# motor_drive.net
KiCad netlist of a schematic drawn in Altium Designer
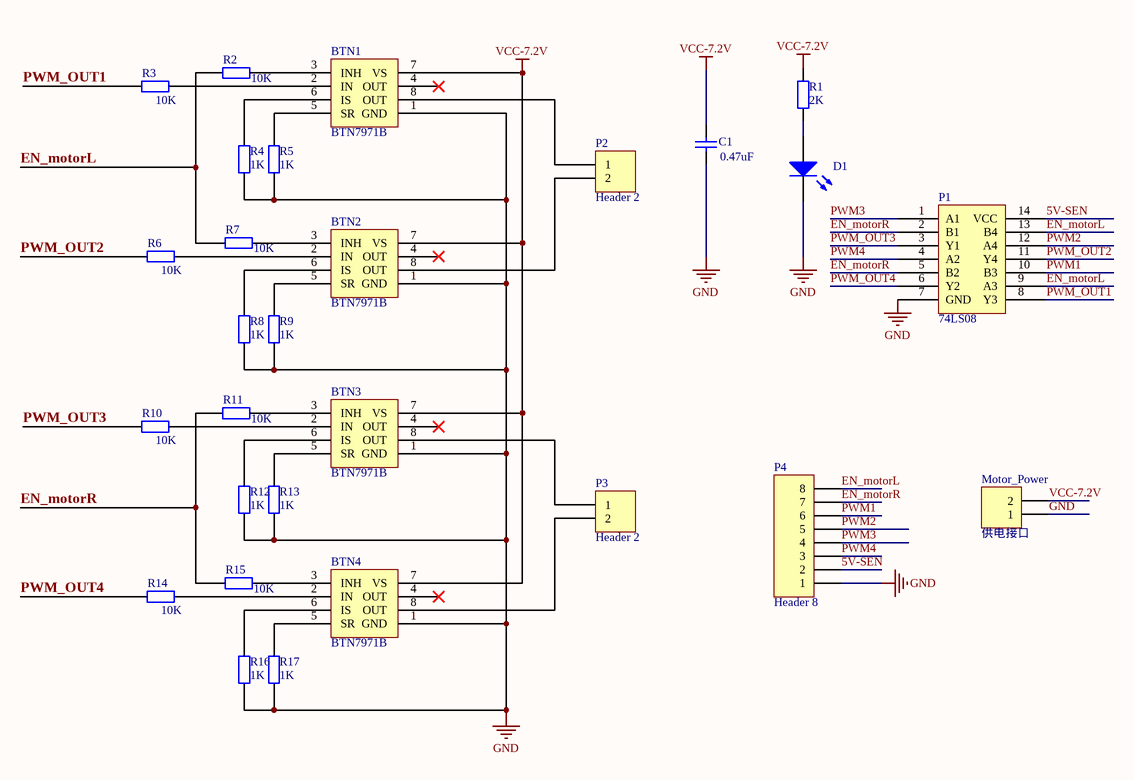
[diagram p0: motor_drive.SchDoc]

(export (version "E")
  (design (tool "Eeschema 10.0.6"))
  (components
    (comp (ref "BTN1") (value "BTN7971B") (footprint "TO-263-7") (libsource (lib "") (part "Component_1_1")))
    (comp (ref "BTN2") (value "BTN7971B") (footprint "TO-263-7") (libsource (lib "") (part "Component_1_1")))
    (comp (ref "BTN3") (value "BTN7971B") (footprint "TO-263-7") (libsource (lib "") (part "Component_1_1")))
    (comp (ref "BTN4") (value "BTN7971B") (footprint "TO-263-7") (libsource (lib "") (part "Component_1_1")))
    (comp (ref "C1")
      (value "0.47uF")
      (footprint "3216")
      (description "Capacitor")
      (fields (field (name "Comment") "Cap") (field (name "PUBLISHER") "Altium Limited"))
      (libsource (lib "Miscellaneous Devices") (part "Cap"))
    )
    (comp (ref "D1")
      (value "LED3")
      (footprint "C-0805")
      (description "Typical BLUE SiC LED")
      (fields (field (name "PUBLISHER") "Altium Limited"))
      (libsource (lib "Miscellaneous Devices") (part "LED3"))
    )
    (comp (ref "Motor_Power")
      (value "供电接口")
      (footprint "P_Header")
      (description "Header, 2-Pin")
      (fields (field (name "PUBLISHER") "Altium Limited"))
      (libsource (lib "Miscellaneous Connectors") (part "Header 2"))
    )
    (comp (ref "P1") (value "74LS08") (footprint "DIP-14") (libsource (lib "库1") (part "Component_1")))
    (comp (ref "P2")
      (value "Header 2")
      (footprint "PCBComponent_1")
      (libsource (lib "Schlib1") (part "Component_1"))
    )
    (comp (ref "P3")
      (value "Header 2")
      (footprint "PCBComponent_1")
      (libsource (lib "Schlib1") (part "Component_1"))
    )
    (comp (ref "P4")
      (value "Header 8")
      (footprint "HDR1X8")
      (description "Header, 8-Pin")
      (fields (field (name "PUBLISHER") "Altium Limited"))
      (libsource (lib "Miscellaneous Connectors") (part "Header 8"))
    )
    (comp (ref "R1")
      (value "2K")
      (footprint "0805")
      (description "Resistor")
      (fields (field (name "Comment") "Res2") (field (name "PUBLISHER") "Altium Limited"))
      (libsource (lib "Miscellaneous Devices") (part "Res2"))
    )
    (comp (ref "R2")
      (value "10K")
      (footprint "0805")
      (description "Resistor")
      (fields (field (name "Comment") "Res2") (field (name "PUBLISHER") "Altium Limited"))
      (libsource (lib "") (part "Res2_1"))
    )
    (comp (ref "R3")
      (value "10K")
      (footprint "0805")
      (description "Resistor")
      (fields (field (name "Comment") "Res2") (field (name "PUBLISHER") "Altium Limited"))
      (libsource (lib "") (part "Res2_1"))
    )
    (comp (ref "R4")
      (value "1K")
      (footprint "0805")
      (description "Resistor")
      (fields (field (name "Comment") "Res2") (field (name "PUBLISHER") "Altium Limited"))
      (libsource (lib "Miscellaneous Devices") (part "Res2"))
    )
    (comp (ref "R5")
      (value "1K")
      (footprint "0805")
      (description "Resistor")
      (fields (field (name "Comment") "Res2") (field (name "PUBLISHER") "Altium Limited"))
      (libsource (lib "Miscellaneous Devices") (part "Res2"))
    )
    (comp (ref "R6")
      (value "10K")
      (footprint "0805")
      (description "Resistor")
      (fields (field (name "Comment") "Res2") (field (name "PUBLISHER") "Altium Limited"))
      (libsource (lib "") (part "Res2_1"))
    )
    (comp (ref "R7")
      (value "10K")
      (footprint "0805")
      (description "Resistor")
      (fields (field (name "Comment") "Res2") (field (name "PUBLISHER") "Altium Limited"))
      (libsource (lib "") (part "Res2_1"))
    )
    (comp (ref "R8")
      (value "1K")
      (footprint "0805")
      (description "Resistor")
      (fields (field (name "Comment") "Res2") (field (name "PUBLISHER") "Altium Limited"))
      (libsource (lib "Miscellaneous Devices") (part "Res2"))
    )
    (comp (ref "R9")
      (value "1K")
      (footprint "0805")
      (description "Resistor")
      (fields (field (name "Comment") "Res2") (field (name "PUBLISHER") "Altium Limited"))
      (libsource (lib "Miscellaneous Devices") (part "Res2"))
    )
    (comp (ref "R10")
      (value "10K")
      (footprint "0805")
      (description "Resistor")
      (fields (field (name "Comment") "Res2") (field (name "PUBLISHER") "Altium Limited"))
      (libsource (lib "") (part "Res2_1"))
    )
    (comp (ref "R11")
      (value "10K")
      (footprint "0805")
      (description "Resistor")
      (fields (field (name "Comment") "Res2") (field (name "PUBLISHER") "Altium Limited"))
      (libsource (lib "") (part "Res2_1"))
    )
    (comp (ref "R12")
      (value "1K")
      (footprint "0805")
      (description "Resistor")
      (fields (field (name "Comment") "Res2") (field (name "PUBLISHER") "Altium Limited"))
      (libsource (lib "Miscellaneous Devices") (part "Res2"))
    )
    (comp (ref "R13")
      (value "1K")
      (footprint "0805")
      (description "Resistor")
      (fields (field (name "Comment") "Res2") (field (name "PUBLISHER") "Altium Limited"))
      (libsource (lib "Miscellaneous Devices") (part "Res2"))
    )
    (comp (ref "R14")
      (value "10K")
      (footprint "0805")
      (description "Resistor")
      (fields (field (name "Comment") "Res2") (field (name "PUBLISHER") "Altium Limited"))
      (libsource (lib "") (part "Res2_1"))
    )
    (comp (ref "R15")
      (value "10K")
      (footprint "0805")
      (description "Resistor")
      (fields (field (name "Comment") "Res2") (field (name "PUBLISHER") "Altium Limited"))
      (libsource (lib "") (part "Res2_1"))
    )
    (comp (ref "R16")
      (value "1K")
      (footprint "0805")
      (description "Resistor")
      (fields (field (name "Comment") "Res2") (field (name "PUBLISHER") "Altium Limited"))
      (libsource (lib "Miscellaneous Devices") (part "Res2"))
    )
    (comp (ref "R17")
      (value "1K")
      (footprint "0805")
      (description "Resistor")
      (fields (field (name "Comment") "Res2") (field (name "PUBLISHER") "Altium Limited"))
      (libsource (lib "Miscellaneous Devices") (part "Res2"))
    )
  )
  (nets
    (net (code "1") (name "/5V-SEN") (class "Default")
      (node (ref "P1") (pin "14") (pinfunction "VCC_14") (pintype "passive"))
      (node (ref "P4") (pin "2") (pinfunction "2_2") (pintype "passive"))
    )
    (net (code "2") (name "/EN_motorL") (class "Default")
      (node (ref "P1") (pin "13") (pinfunction "B4_13") (pintype "passive"))
      (node (ref "P1") (pin "9") (pinfunction "A3_9") (pintype "passive"))
      (node (ref "P4") (pin "8") (pinfunction "8_8") (pintype "passive"))
      (node (ref "R2") (pin "1") (pinfunction "1_1") (pintype "passive"))
      (node (ref "R7") (pin "1") (pinfunction "1_1") (pintype "passive"))
    )
    (net (code "3") (name "/EN_motorR") (class "Default")
      (node (ref "P1") (pin "2") (pinfunction "B1_2") (pintype "passive"))
      (node (ref "P1") (pin "5") (pinfunction "B2_5") (pintype "passive"))
      (node (ref "P4") (pin "7") (pinfunction "7_7") (pintype "passive"))
      (node (ref "R11") (pin "1") (pinfunction "1_1") (pintype "passive"))
      (node (ref "R15") (pin "1") (pinfunction "1_1") (pintype "passive"))
    )
    (net (code "4") (name "/PWM1") (class "Default")
      (node (ref "P1") (pin "10") (pinfunction "B3_10") (pintype "passive"))
      (node (ref "P4") (pin "6") (pinfunction "6_6") (pintype "passive"))
    )
    (net (code "5") (name "/PWM2") (class "Default")
      (node (ref "P1") (pin "12") (pinfunction "A4_12") (pintype "passive"))
      (node (ref "P4") (pin "5") (pinfunction "5_5") (pintype "passive"))
    )
    (net (code "6") (name "/PWM3") (class "Default")
      (node (ref "P1") (pin "1") (pinfunction "A1_1") (pintype "passive"))
      (node (ref "P4") (pin "4") (pinfunction "4_4") (pintype "passive"))
    )
    (net (code "7") (name "/PWM4") (class "Default")
      (node (ref "P1") (pin "4") (pinfunction "A2_4") (pintype "passive"))
      (node (ref "P4") (pin "3") (pinfunction "3_3") (pintype "passive"))
    )
    (net (code "8") (name "/PWM_OUT1") (class "Default")
      (node (ref "P1") (pin "8") (pinfunction "Y3_8") (pintype "passive"))
      (node (ref "R3") (pin "1") (pinfunction "1_1") (pintype "passive"))
    )
    (net (code "9") (name "/PWM_OUT2") (class "Default")
      (node (ref "P1") (pin "11") (pinfunction "Y4_11") (pintype "passive"))
      (node (ref "R6") (pin "1") (pinfunction "1_1") (pintype "passive"))
    )
    (net (code "10") (name "/PWM_OUT3") (class "Default")
      (node (ref "P1") (pin "3") (pinfunction "Y1_3") (pintype "passive"))
      (node (ref "R10") (pin "1") (pinfunction "1_1") (pintype "passive"))
    )
    (net (code "11") (name "/PWM_OUT4") (class "Default")
      (node (ref "P1") (pin "6") (pinfunction "Y2_6") (pintype "passive"))
      (node (ref "R14") (pin "1") (pinfunction "1_1") (pintype "passive"))
    )
    (net (code "12") (name "GND") (class "Default")
      (node (ref "BTN1") (pin "1") (pinfunction "GND_1") (pintype "passive"))
      (node (ref "BTN2") (pin "1") (pinfunction "GND_1") (pintype "passive"))
      (node (ref "BTN3") (pin "1") (pinfunction "GND_1") (pintype "passive"))
      (node (ref "BTN4") (pin "1") (pinfunction "GND_1") (pintype "passive"))
      (node (ref "C1") (pin "1") (pinfunction "1_1") (pintype "passive"))
      (node (ref "D1") (pin "2") (pinfunction "K_2") (pintype "passive"))
      (node (ref "Motor_Power") (pin "1") (pinfunction "1_1") (pintype "passive"))
      (node (ref "P1") (pin "7") (pinfunction "GND_7") (pintype "passive"))
      (node (ref "P4") (pin "1") (pinfunction "1_1") (pintype "passive"))
      (node (ref "R12") (pin "1") (pinfunction "1_1") (pintype "passive"))
      (node (ref "R13") (pin "1") (pinfunction "1_1") (pintype "passive"))
      (node (ref "R16") (pin "1") (pinfunction "1_1") (pintype "passive"))
      (node (ref "R17") (pin "1") (pinfunction "1_1") (pintype "passive"))
      (node (ref "R4") (pin "1") (pinfunction "1_1") (pintype "passive"))
      (node (ref "R5") (pin "1") (pinfunction "1_1") (pintype "passive"))
      (node (ref "R8") (pin "1") (pinfunction "1_1") (pintype "passive"))
      (node (ref "R9") (pin "1") (pinfunction "1_1") (pintype "passive"))
    )
    (net (code "13") (name "Net-(BTN1-IN)") (class "Default")
      (node (ref "BTN1") (pin "2") (pinfunction "IN_2") (pintype "passive"))
      (node (ref "R3") (pin "2") (pinfunction "2_2") (pintype "passive"))
    )
    (net (code "14") (name "Net-(BTN1-INH)") (class "Default")
      (node (ref "BTN1") (pin "3") (pinfunction "INH_3") (pintype "passive"))
      (node (ref "R2") (pin "2") (pinfunction "2_2") (pintype "passive"))
    )
    (net (code "15") (name "Net-(BTN1-IS)") (class "Default")
      (node (ref "BTN1") (pin "6") (pinfunction "IS_6") (pintype "passive"))
      (node (ref "R4") (pin "2") (pinfunction "2_2") (pintype "passive"))
    )
    (net (code "16") (name "Net-(BTN1-OUT-Pad8)") (class "Default")
      (node (ref "BTN1") (pin "8") (pinfunction "OUT_8") (pintype "passive"))
      (node (ref "P2") (pin "1") (pinfunction "1_1") (pintype "passive"))
    )
    (net (code "17") (name "Net-(BTN1-SR)") (class "Default")
      (node (ref "BTN1") (pin "5") (pinfunction "SR_5") (pintype "passive"))
      (node (ref "R5") (pin "2") (pinfunction "2_2") (pintype "passive"))
    )
    (net (code "18") (name "Net-(BTN2-IN)") (class "Default")
      (node (ref "BTN2") (pin "2") (pinfunction "IN_2") (pintype "passive"))
      (node (ref "R6") (pin "2") (pinfunction "2_2") (pintype "passive"))
    )
    (net (code "19") (name "Net-(BTN2-INH)") (class "Default")
      (node (ref "BTN2") (pin "3") (pinfunction "INH_3") (pintype "passive"))
      (node (ref "R7") (pin "2") (pinfunction "2_2") (pintype "passive"))
    )
    (net (code "20") (name "Net-(BTN2-IS)") (class "Default")
      (node (ref "BTN2") (pin "6") (pinfunction "IS_6") (pintype "passive"))
      (node (ref "R8") (pin "2") (pinfunction "2_2") (pintype "passive"))
    )
    (net (code "21") (name "Net-(BTN2-OUT-Pad8)") (class "Default")
      (node (ref "BTN2") (pin "8") (pinfunction "OUT_8") (pintype "passive"))
      (node (ref "P2") (pin "2") (pinfunction "2_2") (pintype "passive"))
    )
    (net (code "22") (name "Net-(BTN2-SR)") (class "Default")
      (node (ref "BTN2") (pin "5") (pinfunction "SR_5") (pintype "passive"))
      (node (ref "R9") (pin "2") (pinfunction "2_2") (pintype "passive"))
    )
    (net (code "23") (name "Net-(BTN3-IN)") (class "Default")
      (node (ref "BTN3") (pin "2") (pinfunction "IN_2") (pintype "passive"))
      (node (ref "R10") (pin "2") (pinfunction "2_2") (pintype "passive"))
    )
    (net (code "24") (name "Net-(BTN3-INH)") (class "Default")
      (node (ref "BTN3") (pin "3") (pinfunction "INH_3") (pintype "passive"))
      (node (ref "R11") (pin "2") (pinfunction "2_2") (pintype "passive"))
    )
    (net (code "25") (name "Net-(BTN3-IS)") (class "Default")
      (node (ref "BTN3") (pin "6") (pinfunction "IS_6") (pintype "passive"))
      (node (ref "R12") (pin "2") (pinfunction "2_2") (pintype "passive"))
    )
    (net (code "26") (name "Net-(BTN3-OUT-Pad8)") (class "Default")
      (node (ref "BTN3") (pin "8") (pinfunction "OUT_8") (pintype "passive"))
      (node (ref "P3") (pin "1") (pinfunction "1_1") (pintype "passive"))
    )
    (net (code "27") (name "Net-(BTN3-SR)") (class "Default")
      (node (ref "BTN3") (pin "5") (pinfunction "SR_5") (pintype "passive"))
      (node (ref "R13") (pin "2") (pinfunction "2_2") (pintype "passive"))
    )
    (net (code "28") (name "Net-(BTN4-IN)") (class "Default")
      (node (ref "BTN4") (pin "2") (pinfunction "IN_2") (pintype "passive"))
      (node (ref "R14") (pin "2") (pinfunction "2_2") (pintype "passive"))
    )
    (net (code "29") (name "Net-(BTN4-INH)") (class "Default")
      (node (ref "BTN4") (pin "3") (pinfunction "INH_3") (pintype "passive"))
      (node (ref "R15") (pin "2") (pinfunction "2_2") (pintype "passive"))
    )
    (net (code "30") (name "Net-(BTN4-IS)") (class "Default")
      (node (ref "BTN4") (pin "6") (pinfunction "IS_6") (pintype "passive"))
      (node (ref "R16") (pin "2") (pinfunction "2_2") (pintype "passive"))
    )
    (net (code "31") (name "Net-(BTN4-OUT-Pad8)") (class "Default")
      (node (ref "BTN4") (pin "8") (pinfunction "OUT_8") (pintype "passive"))
      (node (ref "P3") (pin "2") (pinfunction "2_2") (pintype "passive"))
    )
    (net (code "32") (name "Net-(BTN4-SR)") (class "Default")
      (node (ref "BTN4") (pin "5") (pinfunction "SR_5") (pintype "passive"))
      (node (ref "R17") (pin "2") (pinfunction "2_2") (pintype "passive"))
    )
    (net (code "33") (name "Net-(D1-A)") (class "Default")
      (node (ref "D1") (pin "1") (pinfunction "A_1") (pintype "passive"))
      (node (ref "R1") (pin "1") (pinfunction "1_1") (pintype "passive"))
    )
    (net (code "34") (name "VCC-7.2V") (class "Default")
      (node (ref "BTN1") (pin "7") (pinfunction "VS_7") (pintype "passive"))
      (node (ref "BTN2") (pin "7") (pinfunction "VS_7") (pintype "passive"))
      (node (ref "BTN3") (pin "7") (pinfunction "VS_7") (pintype "passive"))
      (node (ref "BTN4") (pin "7") (pinfunction "VS_7") (pintype "passive"))
      (node (ref "C1") (pin "2") (pinfunction "2_2") (pintype "passive"))
      (node (ref "Motor_Power") (pin "2") (pinfunction "2_2") (pintype "passive"))
      (node (ref "R1") (pin "2") (pinfunction "2_2") (pintype "passive"))
    )
    (net (code "35") (name "unconnected-(BTN1-OUT-Pad4)") (class "Default")
      (node (ref "BTN1") (pin "4") (pinfunction "OUT_4") (pintype "passive+no_connect"))
    )
    (net (code "36") (name "unconnected-(BTN2-OUT-Pad4)") (class "Default")
      (node (ref "BTN2") (pin "4") (pinfunction "OUT_4") (pintype "passive+no_connect"))
    )
    (net (code "37") (name "unconnected-(BTN3-OUT-Pad4)") (class "Default")
      (node (ref "BTN3") (pin "4") (pinfunction "OUT_4") (pintype "passive+no_connect"))
    )
    (net (code "38") (name "unconnected-(BTN4-OUT-Pad4)") (class "Default")
      (node (ref "BTN4") (pin "4") (pinfunction "OUT_4") (pintype "passive+no_connect"))
    )
  )
)
